# Main_PCB_v2_2.net
KiCad netlist of a schematic drawn in EAGLE
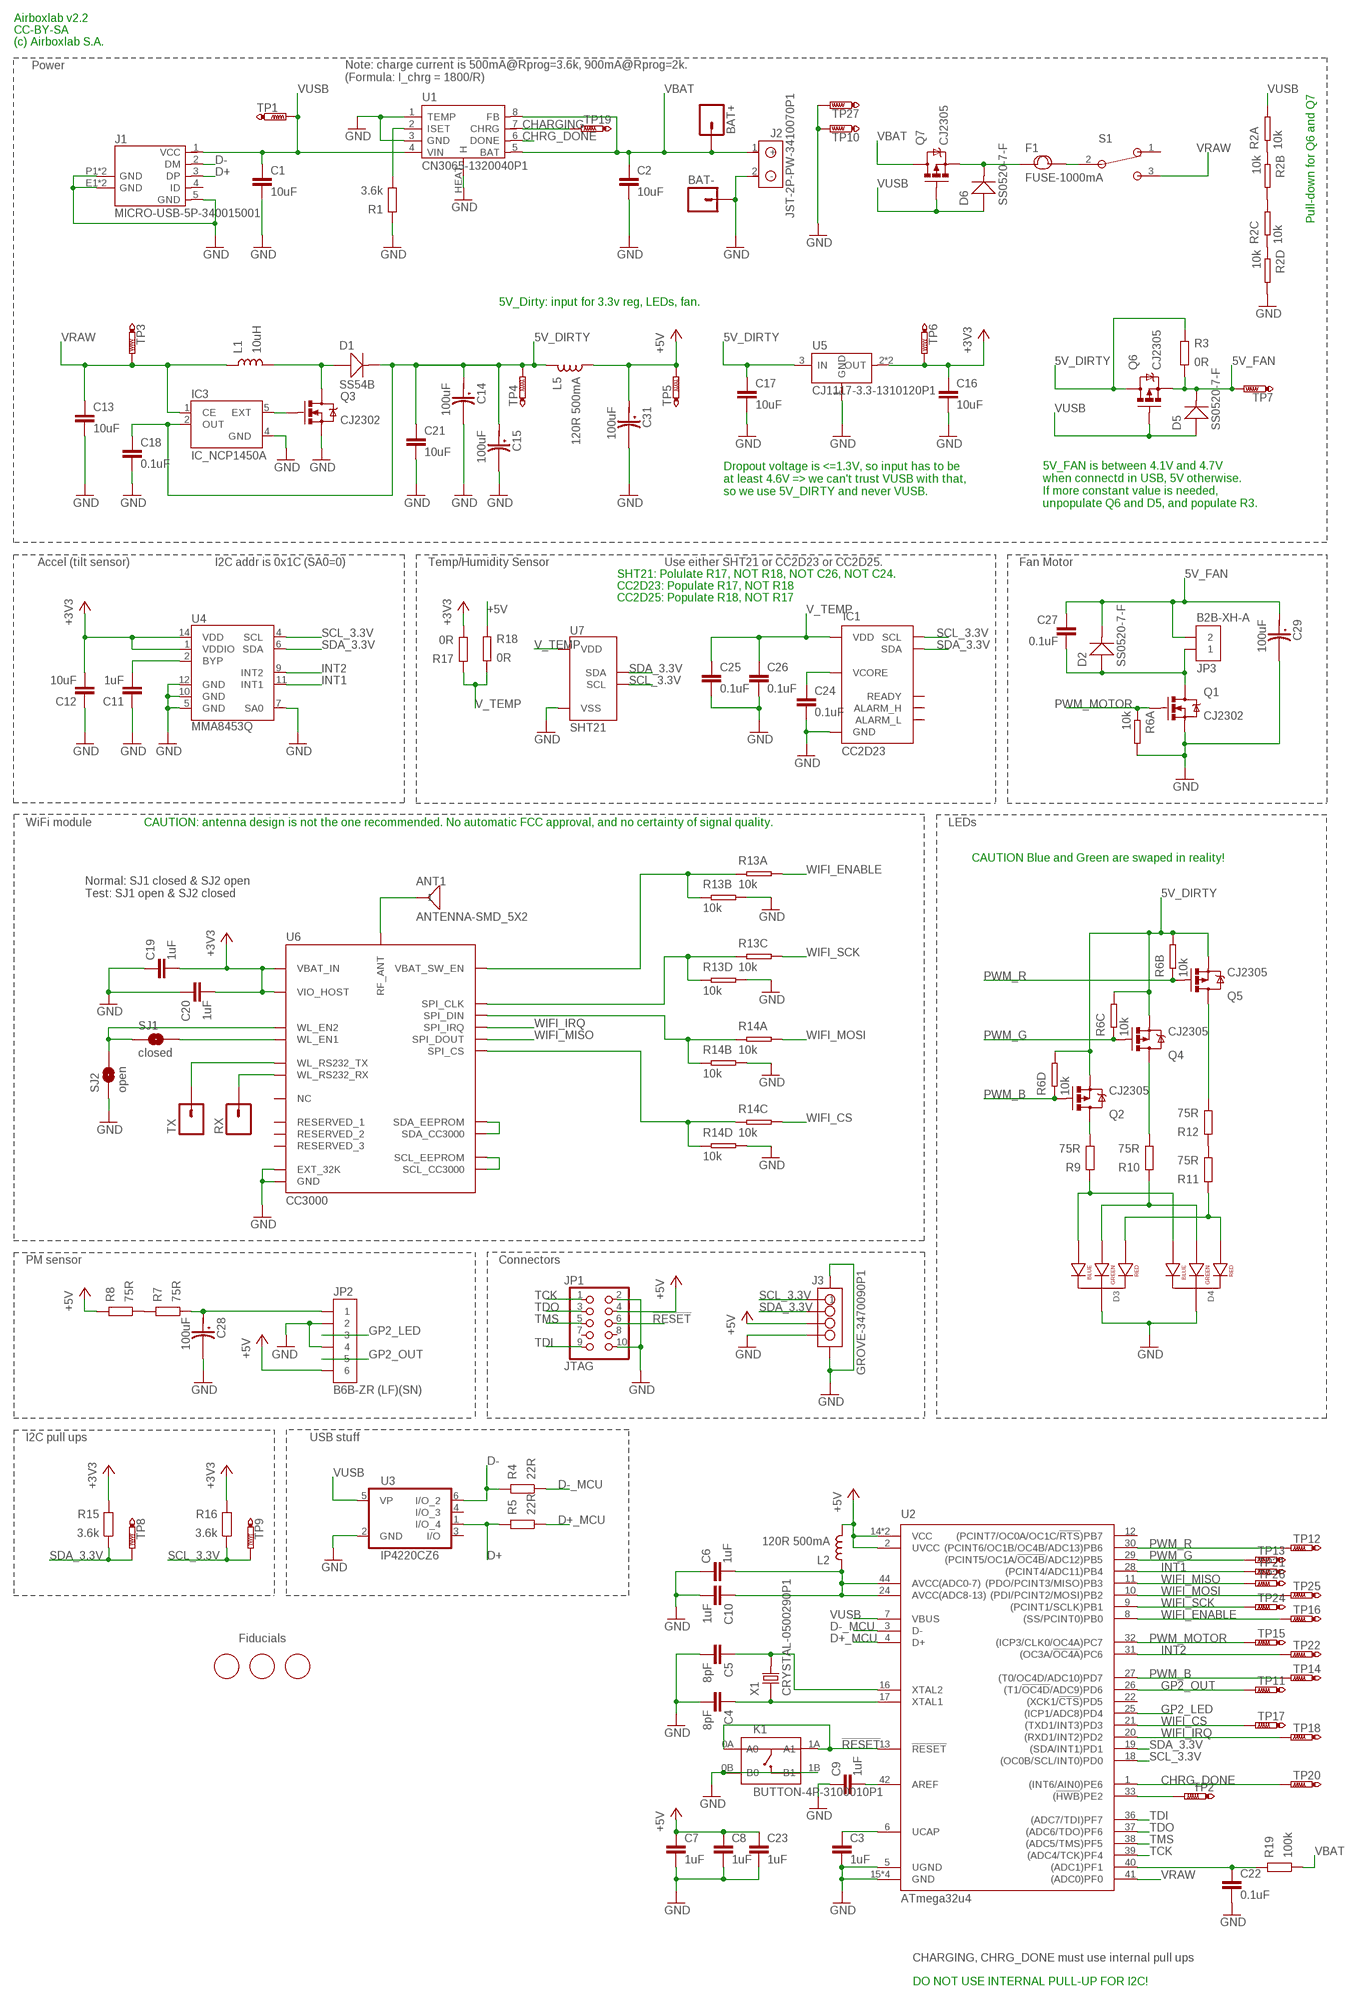
[diagram p0: schematic, sheet 1]

(export (version "E")
  (design (tool "Eeschema 10.0.6"))
  (components
    (comp (ref "ANT1")
      (value "ANTENNA-SMD_5X2")
      (footprint "eagle-import:ANTENNA_SMD_5X2")
      (libsource (lib "eagle-import") (part "ANTENNA-SMD_5X2"))
    )
    (comp (ref "BAT+")
      (value "M01PTH")
      (footprint "eagle-import:1X01")
      (libsource (lib "eagle-import") (part "M01PTH"))
    )
    (comp (ref "BAT-")
      (value "M01PTH")
      (footprint "eagle-import:1X01")
      (libsource (lib "eagle-import") (part "M01PTH"))
    )
    (comp (ref "C1")
      (value "10uF")
      (footprint "eagle-import:0805_N")
      (libsource (lib "eagle-import") (part "C0805"))
    )
    (comp (ref "C2")
      (value "10uF")
      (footprint "eagle-import:0805_N")
      (libsource (lib "eagle-import") (part "C0805"))
    )
    (comp (ref "C3")
      (value "1uF")
      (footprint "eagle-import:0603_N")
      (libsource (lib "eagle-import") (part "C0603"))
    )
    (comp (ref "C4")
      (value "8pF")
      (footprint "eagle-import:0603_N")
      (libsource (lib "eagle-import") (part "C0603"))
    )
    (comp (ref "C5")
      (value "8pF")
      (footprint "eagle-import:0603_N")
      (libsource (lib "eagle-import") (part "C0603"))
    )
    (comp (ref "C6")
      (value "1uF")
      (footprint "eagle-import:0603_N")
      (libsource (lib "eagle-import") (part "C0603"))
    )
    (comp (ref "C7")
      (value "1uF")
      (footprint "eagle-import:0603_N")
      (libsource (lib "eagle-import") (part "C0603"))
    )
    (comp (ref "C8")
      (value "1uF")
      (footprint "eagle-import:0603_N")
      (libsource (lib "eagle-import") (part "C0603"))
    )
    (comp (ref "C9")
      (value "1uF")
      (footprint "eagle-import:0603_N")
      (libsource (lib "eagle-import") (part "C0603"))
    )
    (comp (ref "C10")
      (value "1uF")
      (footprint "eagle-import:0603_N")
      (libsource (lib "eagle-import") (part "C0603"))
    )
    (comp (ref "C11")
      (value "1uF")
      (footprint "eagle-import:0603_N")
      (libsource (lib "eagle-import") (part "C0603"))
    )
    (comp (ref "C12")
      (value "10uF")
      (footprint "eagle-import:0805_N")
      (libsource (lib "eagle-import") (part "C0805"))
    )
    (comp (ref "C13")
      (value "10uF")
      (footprint "eagle-import:0805_N")
      (libsource (lib "eagle-import") (part "C0805"))
    )
    (comp (ref "C14")
      (value "100uF")
      (footprint "eagle-import:AVX-C")
      (libsource (lib "eagle-import") (part "C-POLAR-C"))
    )
    (comp (ref "C15")
      (value "100uF")
      (footprint "eagle-import:AVX-C")
      (libsource (lib "eagle-import") (part "C-POLAR-C"))
    )
    (comp (ref "C16")
      (value "10uF")
      (footprint "eagle-import:0805_N")
      (libsource (lib "eagle-import") (part "C0805"))
    )
    (comp (ref "C17")
      (value "10uF")
      (footprint "eagle-import:0805_N")
      (libsource (lib "eagle-import") (part "C0805"))
    )
    (comp (ref "C18")
      (value "0.1uF")
      (footprint "eagle-import:0603_N")
      (libsource (lib "eagle-import") (part "C0603"))
    )
    (comp (ref "C19")
      (value "1uF")
      (footprint "eagle-import:0603_N")
      (libsource (lib "eagle-import") (part "C0603"))
    )
    (comp (ref "C20")
      (value "1uF")
      (footprint "eagle-import:0603_N")
      (libsource (lib "eagle-import") (part "C0603"))
    )
    (comp (ref "C21")
      (value "10uF")
      (footprint "eagle-import:0805_N")
      (libsource (lib "eagle-import") (part "C0805"))
    )
    (comp (ref "C22")
      (value "0.1uF")
      (footprint "eagle-import:0603_N")
      (libsource (lib "eagle-import") (part "C0603"))
    )
    (comp (ref "C23")
      (value "1uF")
      (footprint "eagle-import:0603_N")
      (libsource (lib "eagle-import") (part "C0603"))
    )
    (comp (ref "C24")
      (value "0.1uF")
      (footprint "eagle-import:0603_N")
      (libsource (lib "eagle-import") (part "C0603"))
    )
    (comp (ref "C25")
      (value "0.1uF")
      (footprint "eagle-import:0603_N")
      (libsource (lib "eagle-import") (part "C0603"))
    )
    (comp (ref "C26")
      (value "0.1uF")
      (footprint "eagle-import:0603_N")
      (libsource (lib "eagle-import") (part "C0603"))
    )
    (comp (ref "C27")
      (value "0.1uF")
      (footprint "eagle-import:0603_N")
      (libsource (lib "eagle-import") (part "C0603"))
    )
    (comp (ref "C28")
      (value "100uF")
      (footprint "eagle-import:AVX-C")
      (libsource (lib "eagle-import") (part "C-POLAR-C"))
    )
    (comp (ref "C29")
      (value "100uF")
      (footprint "eagle-import:AVX-C")
      (libsource (lib "eagle-import") (part "C-POLAR-C"))
    )
    (comp (ref "C31")
      (value "100uF")
      (footprint "eagle-import:AVX-C")
      (libsource (lib "eagle-import") (part "C-POLAR-C"))
    )
    (comp (ref "D1")
      (value "SS54B")
      (footprint "eagle-import:SMB")
      (libsource (lib "eagle-import") (part "D-SMB"))
    )
    (comp (ref "D2")
      (value "SS0520-7-F")
      (footprint "eagle-import:SOD123")
      (libsource (lib "eagle-import") (part "D-SOD-123"))
    )
    (comp (ref "D3")
      (value "LED-RGB-CC-THRUCLEAR")
      (footprint "eagle-import:LED-RGB-THRU")
      (libsource (lib "eagle-import") (part "LED-RGB-CC-THRUCLEAR"))
    )
    (comp (ref "D4")
      (value "LED-RGB-CC-THRUCLEAR")
      (footprint "eagle-import:LED-RGB-THRU")
      (libsource (lib "eagle-import") (part "LED-RGB-CC-THRUCLEAR"))
    )
    (comp (ref "D5")
      (value "SS0520-7-F")
      (footprint "eagle-import:SOD123")
      (libsource (lib "eagle-import") (part "D-SOD-123"))
    )
    (comp (ref "D6")
      (value "SS0520-7-F")
      (footprint "eagle-import:SOD123")
      (libsource (lib "eagle-import") (part "D-SOD-123"))
    )
    (comp (ref "F1")
      (value "FUSE-1000mA")
      (footprint "eagle-import:F1206")
      (libsource (lib "eagle-import") (part "FUSE-1206"))
    )
    (comp (ref "IC1")
      (value "CC2D23")
      (footprint "eagle-import:CC2DXX")
      (libsource (lib "eagle-import") (part "CC2DXX"))
    )
    (comp (ref "IC3")
      (value "IC_NCP1450A")
      (footprint "eagle-import:SOT-23-5_N")
      (libsource (lib "eagle-import") (part "IC_NCP1450A"))
    )
    (comp (ref "J1")
      (value "MICRO-USB-5P-340015001")
      (footprint "eagle-import:B-SMD-5P")
      (libsource (lib "eagle-import") (part "MICRO-USB-5P-340015001"))
    )
    (comp (ref "J2")
      (value "JST-2P-PW-3410070P1")
      (footprint "eagle-import:2P-2.0-90D")
      (libsource (lib "eagle-import") (part "JST-2P-PW-3410070P1"))
    )
    (comp (ref "J3")
      (value "GROVE-3470090P1")
      (footprint "eagle-import:4P-SMD-2.0")
      (libsource (lib "eagle-import") (part "GROVE-4P-2.0-SMD-FEMALE-REINFORCE-3470090P1"))
    )
    (comp (ref "JP1")
      (value "JTAG")
      (footprint "eagle-import:CONNECTOR_2.54MM_5X2_LOCK")
      (libsource (lib "eagle-import") (part "CONNECTOR_5X2_2.54MM_LOCK"))
    )
    (comp (ref "JP2")
      (value "B6B-ZR (LF)(SN)")
      (footprint "eagle-import:CONNECTOR_B6B-ZR")
      (libsource (lib "eagle-import") (part "CONNECTOR_6X1-ZR-THT"))
    )
    (comp (ref "JP3")
      (value "B2B-XH-A")
      (footprint "eagle-import:CONNECTOR_B2B-XH-A")
      (libsource (lib "eagle-import") (part "CONNECTOR_2X1"))
    )
    (comp (ref "K1")
      (value "BUTTON-4P-3100010P1")
      (footprint "eagle-import:4P-SMD-6.0X6.0X5.0H")
      (libsource (lib "eagle-import") (part "BUTTON-4P-3100010P1"))
    )
    (comp (ref "L1")
      (value "10uH")
      (footprint "eagle-import:L_SRU8043")
      (libsource (lib "eagle-import") (part "L-SMD_8X8"))
    )
    (comp (ref "L2")
      (value "120R 500mA")
      (footprint "eagle-import:0603_N")
      (libsource (lib "eagle-import") (part "L0603"))
    )
    (comp (ref "L5")
      (value "120R 500mA")
      (footprint "eagle-import:0603_N")
      (libsource (lib "eagle-import") (part "L0603"))
    )
    (comp (ref "Q1")
      (value "CJ2302")
      (footprint "eagle-import:SOT-23-3_N_SSOT-3_N")
      (libsource (lib "eagle-import") (part "MOSFET_N_SOT23-3"))
    )
    (comp (ref "Q2")
      (value "CJ2305")
      (footprint "eagle-import:SOT-23-3_N_SSOT-3_N")
      (libsource (lib "eagle-import") (part "MOSFET_P_FDN308P"))
    )
    (comp (ref "Q3")
      (value "CJ2302")
      (footprint "eagle-import:SOT-23-3_N_SSOT-3_N")
      (libsource (lib "eagle-import") (part "MOSFET_N_SOT23-3"))
    )
    (comp (ref "Q4")
      (value "CJ2305")
      (footprint "eagle-import:SOT-23-3_N_SSOT-3_N")
      (libsource (lib "eagle-import") (part "MOSFET_P_FDN308P"))
    )
    (comp (ref "Q5")
      (value "CJ2305")
      (footprint "eagle-import:SOT-23-3_N_SSOT-3_N")
      (libsource (lib "eagle-import") (part "MOSFET_P_FDN308P"))
    )
    (comp (ref "Q6")
      (value "CJ2305")
      (footprint "eagle-import:SOT-23-3_N_SSOT-3_N")
      (libsource (lib "eagle-import") (part "MOSFET_P_FDN308P"))
    )
    (comp (ref "Q7")
      (value "CJ2305")
      (footprint "eagle-import:SOT-23-3_N_SSOT-3_N")
      (libsource (lib "eagle-import") (part "MOSFET_P_FDN308P"))
    )
    (comp (ref "R1")
      (value "3.6k")
      (footprint "eagle-import:0603_N")
      (libsource (lib "eagle-import") (part "R0603"))
    )
    (comp (ref "R2")
      (value "10k")
      (footprint "eagle-import:R1206-8")
      (libsource (lib "eagle-import") (part "R-4R"))
    )
    (comp (ref "R3")
      (value "0R")
      (footprint "eagle-import:0603_N")
      (libsource (lib "eagle-import") (part "R0603"))
    )
    (comp (ref "R4")
      (value "22R")
      (footprint "eagle-import:0603_N")
      (libsource (lib "eagle-import") (part "R0603"))
    )
    (comp (ref "R5")
      (value "22R")
      (footprint "eagle-import:0603_N")
      (libsource (lib "eagle-import") (part "R0603"))
    )
    (comp (ref "R6")
      (value "10k")
      (footprint "eagle-import:R1206-8")
      (libsource (lib "eagle-import") (part "R-4R"))
    )
    (comp (ref "R7")
      (value "75R")
      (footprint "eagle-import:0603_N")
      (libsource (lib "eagle-import") (part "R0603"))
    )
    (comp (ref "R8")
      (value "75R")
      (footprint "eagle-import:0603_N")
      (libsource (lib "eagle-import") (part "R0603"))
    )
    (comp (ref "R9")
      (value "75R")
      (footprint "eagle-import:0603_N")
      (libsource (lib "eagle-import") (part "R0603"))
    )
    (comp (ref "R10")
      (value "75R")
      (footprint "eagle-import:0603_N")
      (libsource (lib "eagle-import") (part "R0603"))
    )
    (comp (ref "R11")
      (value "75R")
      (footprint "eagle-import:0603_N")
      (libsource (lib "eagle-import") (part "R0603"))
    )
    (comp (ref "R12")
      (value "75R")
      (footprint "eagle-import:0603_N")
      (libsource (lib "eagle-import") (part "R0603"))
    )
    (comp (ref "R13")
      (value "10k")
      (footprint "eagle-import:R1206-8")
      (libsource (lib "eagle-import") (part "R-4R"))
    )
    (comp (ref "R14")
      (value "10k")
      (footprint "eagle-import:R1206-8")
      (libsource (lib "eagle-import") (part "R-4R"))
    )
    (comp (ref "R15")
      (value "3.6k")
      (footprint "eagle-import:0603_N")
      (libsource (lib "eagle-import") (part "R0603"))
    )
    (comp (ref "R16")
      (value "3.6k")
      (footprint "eagle-import:0603_N")
      (libsource (lib "eagle-import") (part "R0603"))
    )
    (comp (ref "R17")
      (value "0R")
      (footprint "eagle-import:0603_N")
      (libsource (lib "eagle-import") (part "R0603"))
    )
    (comp (ref "R18")
      (value "0R")
      (footprint "eagle-import:0603_N")
      (libsource (lib "eagle-import") (part "R0603"))
    )
    (comp (ref "R19")
      (value "100k")
      (footprint "eagle-import:0603_N")
      (libsource (lib "eagle-import") (part "R0603"))
    )
    (comp (ref "RX")
      (value "M01PTH")
      (footprint "eagle-import:1X01")
      (libsource (lib "eagle-import") (part "M01PTH"))
    )
    (comp (ref "S1")
      (value "SWITCH_SPDT_ON-ON")
      (footprint "eagle-import:SWITCH_SPDT_OS102011MA1QN1")
      (libsource (lib "eagle-import") (part "SWITCH_SPDT_ON-ON"))
    )
    (comp (ref "SJ1")
      (value "closed")
      (footprint "eagle-import:SJ_2S-TRACE2")
      (libsource (lib "eagle-import") (part "SOLDERJUMPER2_TRACE2"))
    )
    (comp (ref "SJ2")
      (value "open")
      (footprint "eagle-import:SJ_2S-NO")
      (libsource (lib "eagle-import") (part "SOLDERJUMPER2NO"))
    )
    (comp (ref "TP1")
      (value "PTR1PAD1-13")
      (footprint "eagle-import:P1-13")
      (libsource (lib "eagle-import") (part "PTR1PAD1-13"))
    )
    (comp (ref "TP2")
      (value "PTR1B1,27")
      (footprint "eagle-import:B1,27")
      (libsource (lib "eagle-import") (part "PTR1B1,27"))
    )
    (comp (ref "TP3")
      (value "PTR1PAD1-13")
      (footprint "eagle-import:P1-13")
      (libsource (lib "eagle-import") (part "PTR1PAD1-13"))
    )
    (comp (ref "TP4")
      (value "PTR1PAD1-13")
      (footprint "eagle-import:P1-13")
      (libsource (lib "eagle-import") (part "PTR1PAD1-13"))
    )
    (comp (ref "TP5")
      (value "PTR1PAD1-13")
      (footprint "eagle-import:P1-13")
      (libsource (lib "eagle-import") (part "PTR1PAD1-13"))
    )
    (comp (ref "TP6")
      (value "PTR1PAD1-13")
      (footprint "eagle-import:P1-13")
      (libsource (lib "eagle-import") (part "PTR1PAD1-13"))
    )
    (comp (ref "TP7")
      (value "PTR1PAD1-13")
      (footprint "eagle-import:P1-13")
      (libsource (lib "eagle-import") (part "PTR1PAD1-13"))
    )
    (comp (ref "TP8")
      (value "PTR1PAD1-13")
      (footprint "eagle-import:P1-13")
      (libsource (lib "eagle-import") (part "PTR1PAD1-13"))
    )
    (comp (ref "TP9")
      (value "PTR1PAD1-13")
      (footprint "eagle-import:P1-13")
      (libsource (lib "eagle-import") (part "PTR1PAD1-13"))
    )
    (comp (ref "TP10")
      (value "PTR1PAD1-13")
      (footprint "eagle-import:P1-13")
      (libsource (lib "eagle-import") (part "PTR1PAD1-13"))
    )
    (comp (ref "TP11")
      (value "PTR1PAD1-13")
      (footprint "eagle-import:P1-13")
      (libsource (lib "eagle-import") (part "PTR1PAD1-13"))
    )
    (comp (ref "TP12")
      (value "PTR1B1,27")
      (footprint "eagle-import:B1,27")
      (libsource (lib "eagle-import") (part "PTR1B1,27"))
    )
    (comp (ref "TP13")
      (value "PTR1B1,27")
      (footprint "eagle-import:B1,27")
      (libsource (lib "eagle-import") (part "PTR1B1,27"))
    )
    (comp (ref "TP14")
      (value "PTR1B1,27")
      (footprint "eagle-import:B1,27")
      (libsource (lib "eagle-import") (part "PTR1B1,27"))
    )
    (comp (ref "TP15")
      (value "PTR1B1,27")
      (footprint "eagle-import:B1,27")
      (libsource (lib "eagle-import") (part "PTR1B1,27"))
    )
    (comp (ref "TP16")
      (value "PTR1B1,27")
      (footprint "eagle-import:B1,27")
      (libsource (lib "eagle-import") (part "PTR1B1,27"))
    )
    (comp (ref "TP17")
      (value "PTR1B1,27")
      (footprint "eagle-import:B1,27")
      (libsource (lib "eagle-import") (part "PTR1B1,27"))
    )
    (comp (ref "TP18")
      (value "PTR1B1,27")
      (footprint "eagle-import:B1,27")
      (libsource (lib "eagle-import") (part "PTR1B1,27"))
    )
    (comp (ref "TP19")
      (value "PTR1B1,27")
      (footprint "eagle-import:B1,27")
      (libsource (lib "eagle-import") (part "PTR1B1,27"))
    )
    (comp (ref "TP20")
      (value "PTR1B1,27")
      (footprint "eagle-import:B1,27")
      (libsource (lib "eagle-import") (part "PTR1B1,27"))
    )
    (comp (ref "TP21")
      (value "PTR1B1,27")
      (footprint "eagle-import:B1,27")
      (libsource (lib "eagle-import") (part "PTR1B1,27"))
    )
    (comp (ref "TP22")
      (value "PTR1B1,27")
      (footprint "eagle-import:B1,27")
      (libsource (lib "eagle-import") (part "PTR1B1,27"))
    )
    (comp (ref "TP24")
      (value "PTR1B1,27")
      (footprint "eagle-import:B1,27")
      (libsource (lib "eagle-import") (part "PTR1B1,27"))
    )
    (comp (ref "TP25")
      (value "PTR1B1,27")
      (footprint "eagle-import:B1,27")
      (libsource (lib "eagle-import") (part "PTR1B1,27"))
    )
    (comp (ref "TP26")
      (value "PTR1B1,27")
      (footprint "eagle-import:B1,27")
      (libsource (lib "eagle-import") (part "PTR1B1,27"))
    )
    (comp (ref "TP27")
      (value "PTR1PAD1-13Y")
      (footprint "eagle-import:P1-13Y")
      (libsource (lib "eagle-import") (part "PTR1PAD1-13Y"))
    )
    (comp (ref "TX")
      (value "M01PTH")
      (footprint "eagle-import:1X01")
      (libsource (lib "eagle-import") (part "M01PTH"))
    )
    (comp (ref "U$1")
      (value "FIDUCIAL")
      (footprint "eagle-import:FIDUCIAL_1MM")
      (libsource (lib "eagle-import") (part "FIDUCIAL"))
    )
    (comp (ref "U$2")
      (value "FIDUCIAL")
      (footprint "eagle-import:FIDUCIAL_1MM")
      (libsource (lib "eagle-import") (part "FIDUCIAL"))
    )
    (comp (ref "U$3")
      (value "FIDUCIAL")
      (footprint "eagle-import:FIDUCIAL_1MM")
      (libsource (lib "eagle-import") (part "FIDUCIAL"))
    )
    (comp (ref "U1")
      (value "CN3065-1320040P1")
      (footprint "eagle-import:DFN8")
      (libsource (lib "eagle-import") (part "CN3065-1320040P1"))
    )
    (comp (ref "U2")
      (value "ATmega32u4")
      (footprint "eagle-import:QFN-44_50P_N")
      (libsource (lib "eagle-import") (part "IC_ATMEGAXXU4-MU"))
    )
    (comp (ref "U3")
      (value "IP4220CZ6")
      (footprint "eagle-import:SOT95P275X110-6N")
      (libsource (lib "eagle-import") (part "IP4220CZ6"))
    )
    (comp (ref "U4")
      (value "MMA8453Q")
      (footprint "eagle-import:QFN-16_0.5MM")
      (libsource (lib "eagle-import") (part "MMA8452Q"))
    )
    (comp (ref "U5")
      (value "CJ1117-3.3-1310120P1")
      (footprint "eagle-import:SOT89")
      (libsource (lib "eagle-import") (part "CJ1117-3.3-1310120P1"))
    )
    (comp (ref "U6")
      (value "CC3000")
      (footprint "eagle-import:CC3000")
      (fields (field (name "AUTHOR") "Matt Bigarani") (field (name "MODIFIED_BY") "Xevelabs"))
      (libsource (lib "eagle-import") (part "CC3000"))
    )
    (comp (ref "U7")
      (value "SHT21")
      (footprint "eagle-import:SHT2X")
      (libsource (lib "eagle-import") (part "SHT2X-21"))
    )
    (comp (ref "X1")
      (value "CRYSTAL-0500290P1")
      (footprint "eagle-import:2P-SMD-5.0X3.2")
      (libsource (lib "eagle-import") (part "CRYSTAL-0500290P1"))
    )
  )
  (nets
    (net (code "1") (name "+3V3") (class "Default")
      (node (ref "C12") (pin "2") (pinfunction "2_2") (pintype "passive"))
      (node (ref "C16") (pin "1") (pinfunction "1_1") (pintype "passive"))
      (node (ref "C19") (pin "2") (pinfunction "2_2") (pintype "passive"))
      (node (ref "C20") (pin "2") (pinfunction "2_2") (pintype "passive"))
      (node (ref "R15") (pin "2") (pinfunction "2_2") (pintype "passive"))
      (node (ref "R16") (pin "2") (pinfunction "2_2") (pintype "passive"))
      (node (ref "R17") (pin "1") (pinfunction "1_1") (pintype "passive"))
      (node (ref "TP6") (pin "TP") (pinfunction "TP_TP") (pintype "input"))
      (node (ref "U4") (pin "1") (pinfunction "VDDIO_1") (pintype "bidirectional"))
      (node (ref "U4") (pin "14") (pinfunction "VDD_14") (pintype "bidirectional"))
      (node (ref "U5") (pin "2") (pinfunction "OUT_2") (pintype "bidirectional"))
      (node (ref "U5") (pin "4") (pinfunction "OUT_4") (pintype "bidirectional"))
      (node (ref "U6") (pin "P$19") (pinfunction "VBAT_IN_P$19") (pintype "bidirectional"))
      (node (ref "U6") (pin "P$23") (pinfunction "VIO_HOST_P$23") (pintype "bidirectional"))
    )
    (net (code "2") (name "+5V") (class "Default")
      (node (ref "C23") (pin "1") (pinfunction "1_1") (pintype "passive"))
      (node (ref "C31") (pin "+") (pinfunction "1_+") (pintype "bidirectional"))
      (node (ref "C7") (pin "1") (pinfunction "1_1") (pintype "passive"))
      (node (ref "C8") (pin "1") (pinfunction "1_1") (pintype "passive"))
      (node (ref "J3") (pin "3") (pinfunction "3_3") (pintype "bidirectional"))
      (node (ref "JP1") (pin "4") (pinfunction "4_4") (pintype "passive"))
      (node (ref "JP2") (pin "P$6") (pinfunction "6_P$6") (pintype "bidirectional"))
      (node (ref "L2") (pin "2") (pinfunction "2_2") (pintype "passive"))
      (node (ref "L5") (pin "2") (pinfunction "2_2") (pintype "passive"))
      (node (ref "R18") (pin "2") (pinfunction "2_2") (pintype "passive"))
      (node (ref "R8") (pin "2") (pinfunction "2_2") (pintype "passive"))
      (node (ref "TP5") (pin "TP") (pinfunction "TP_TP") (pintype "input"))
      (node (ref "U2") (pin "14") (pinfunction "VCC_14") (pintype "power_in"))
      (node (ref "U2") (pin "2") (pinfunction "UVCC_2") (pintype "power_in"))
      (node (ref "U2") (pin "34") (pinfunction "VCC_34") (pintype "power_in"))
    )
    (net (code "3") (name "/5V_DIRTY") (class "Default")
      (node (ref "C14") (pin "+") (pinfunction "1_+") (pintype "bidirectional"))
      (node (ref "C15") (pin "+") (pinfunction "1_+") (pintype "bidirectional"))
      (node (ref "C17") (pin "1") (pinfunction "1_1") (pintype "passive"))
      (node (ref "C18") (pin "1") (pinfunction "1_1") (pintype "passive"))
      (node (ref "C21") (pin "1") (pinfunction "1_1") (pintype "passive"))
      (node (ref "D1") (pin "-") (pinfunction "-_-") (pintype "passive"))
      (node (ref "IC3") (pin "2") (pinfunction "OUT_2") (pintype "input"))
      (node (ref "L5") (pin "1") (pinfunction "1_1") (pintype "passive"))
      (node (ref "Q2") (pin "2") (pinfunction "S_2") (pintype "passive"))
      (node (ref "Q4") (pin "2") (pinfunction "S_2") (pintype "passive"))
      (node (ref "Q5") (pin "2") (pinfunction "S_2") (pintype "passive"))
      (node (ref "Q6") (pin "3") (pinfunction "D_3") (pintype "passive"))
      (node (ref "R3") (pin "2") (pinfunction "2_2") (pintype "passive"))
      (node (ref "R6") (pin "5") (pinfunction "2_5") (pintype "passive"))
      (node (ref "R6") (pin "6") (pinfunction "2_6") (pintype "passive"))
      (node (ref "R6") (pin "7") (pinfunction "2_7") (pintype "passive"))
      (node (ref "TP4") (pin "TP") (pinfunction "TP_TP") (pintype "input"))
      (node (ref "U5") (pin "3") (pinfunction "IN_3") (pintype "bidirectional"))
    )
    (net (code "4") (name "/5V_FAN") (class "Default")
      (node (ref "C27") (pin "1") (pinfunction "1_1") (pintype "passive"))
      (node (ref "C29") (pin "+") (pinfunction "1_+") (pintype "bidirectional"))
      (node (ref "D2") (pin "-") (pinfunction "-_-") (pintype "passive"))
      (node (ref "D5") (pin "-") (pinfunction "-_-") (pintype "passive"))
      (node (ref "JP3") (pin "2") (pinfunction "2_2") (pintype "bidirectional"))
      (node (ref "Q6") (pin "2") (pinfunction "S_2") (pintype "passive"))
      (node (ref "R3") (pin "1") (pinfunction "1_1") (pintype "passive"))
      (node (ref "TP7") (pin "TP") (pinfunction "TP_TP") (pintype "input"))
    )
    (net (code "5") (name "/CHARGING") (class "Default")
      (node (ref "TP19") (pin "TP") (pinfunction "TP_TP") (pintype "input"))
      (node (ref "U1") (pin "7") (pinfunction "CHRG_7") (pintype "bidirectional"))
    )
    (net (code "6") (name "/CHRG_DONE") (class "Default")
      (node (ref "TP20") (pin "TP") (pinfunction "TP_TP") (pintype "input"))
      (node (ref "U1") (pin "6") (pinfunction "DONE_6") (pintype "bidirectional"))
      (node (ref "U2") (pin "1") (pinfunction "(INT6/AIN0)PE6_1") (pintype "bidirectional"))
    )
    (net (code "7") (name "/D+") (class "Default")
      (node (ref "J1") (pin "3") (pinfunction "DP_3") (pintype "bidirectional"))
      (node (ref "R5") (pin "2") (pinfunction "2_2") (pintype "passive"))
      (node (ref "U3") (pin "1") (pinfunction "I/O_4_1") (pintype "bidirectional"))
    )
    (net (code "8") (name "/D+_MCU") (class "Default")
      (node (ref "R5") (pin "1") (pinfunction "1_1") (pintype "passive"))
      (node (ref "U2") (pin "4") (pinfunction "D+_4") (pintype "bidirectional"))
    )
    (net (code "9") (name "/D-") (class "Default")
      (node (ref "J1") (pin "2") (pinfunction "DM_2") (pintype "bidirectional"))
      (node (ref "R4") (pin "2") (pinfunction "2_2") (pintype "passive"))
      (node (ref "U3") (pin "6") (pinfunction "I/O_2_6") (pintype "bidirectional"))
    )
    (net (code "10") (name "/D-_MCU") (class "Default")
      (node (ref "R4") (pin "1") (pinfunction "1_1") (pintype "passive"))
      (node (ref "U2") (pin "3") (pinfunction "D-_3") (pintype "bidirectional"))
    )
    (net (code "11") (name "/GP2_LED") (class "Default")
      (node (ref "JP2") (pin "P$3") (pinfunction "3_P$3") (pintype "bidirectional"))
      (node (ref "U2") (pin "25") (pinfunction "(ICP1/ADC8)PD4_25") (pintype "bidirectional"))
    )
    (net (code "12") (name "/GP2_OUT") (class "Default")
      (node (ref "JP2") (pin "P$5") (pinfunction "5_P$5") (pintype "bidirectional"))
      (node (ref "TP11") (pin "TP") (pinfunction "TP_TP") (pintype "input"))
      (node (ref "U2") (pin "26") (pinfunction "(T1/~{OC4D}/ADC9)PD6_26") (pintype "bidirectional"))
    )
    (net (code "13") (name "/INT1") (class "Default")
      (node (ref "TP21") (pin "TP") (pinfunction "TP_TP") (pintype "input"))
      (node (ref "U2") (pin "28") (pinfunction "(PCINT4/ADC11)PB4_28") (pintype "bidirectional"))
      (node (ref "U4") (pin "11") (pinfunction "INT1_11") (pintype "bidirectional"))
    )
    (net (code "14") (name "/INT2") (class "Default")
      (node (ref "TP22") (pin "TP") (pinfunction "TP_TP") (pintype "input"))
      (node (ref "U2") (pin "31") (pinfunction "(OC3A/~{OC4A})PC6_31") (pintype "output"))
      (node (ref "U4") (pin "9") (pinfunction "INT2_9") (pintype "bidirectional"))
    )
    (net (code "15") (name "/PWM_B") (class "Default")
      (node (ref "Q2") (pin "1") (pinfunction "G_1") (pintype "passive"))
      (node (ref "R6") (pin "4") (pinfunction "1_4") (pintype "passive"))
      (node (ref "TP14") (pin "TP") (pinfunction "TP_TP") (pintype "input"))
      (node (ref "U2") (pin "27") (pinfunction "(T0/OC4D/ADC10)PD7_27") (pintype "bidirectional"))
    )
    (net (code "16") (name "/PWM_G") (class "Default")
      (node (ref "Q4") (pin "1") (pinfunction "G_1") (pintype "passive"))
      (node (ref "R6") (pin "3") (pinfunction "1_3") (pintype "passive"))
      (node (ref "TP13") (pin "TP") (pinfunction "TP_TP") (pintype "input"))
      (node (ref "U2") (pin "29") (pinfunction "(PCINT5/OC1A/~{OC4B}/ADC12)PB5_29") (pintype "bidirectional"))
    )
    (net (code "17") (name "/PWM_MOTOR") (class "Default")
      (node (ref "Q1") (pin "1") (pinfunction "G_1") (pintype "passive"))
      (node (ref "R6") (pin "1") (pinfunction "1_1") (pintype "passive"))
      (node (ref "TP15") (pin "TP") (pinfunction "TP_TP") (pintype "input"))
      (node (ref "U2") (pin "32") (pinfunction "(ICP3/CLK0/OC4A)PC7_32") (pintype "output"))
    )
    (net (code "18") (name "/PWM_R") (class "Default")
      (node (ref "Q5") (pin "1") (pinfunction "G_1") (pintype "passive"))
      (node (ref "R6") (pin "2") (pinfunction "1_2") (pintype "passive"))
      (node (ref "TP12") (pin "TP") (pinfunction "TP_TP") (pintype "input"))
      (node (ref "U2") (pin "30") (pinfunction "(PCINT6/OC1B/OC4B/ADC13)PB6_30") (pintype "bidirectional"))
    )
    (net (code "19") (name "/SCL_3.3V") (class "Default")
      (node (ref "IC1") (pin "P$4") (pinfunction "SCL_P$4") (pintype "bidirectional"))
      (node (ref "J3") (pin "1") (pinfunction "1_1") (pintype "bidirectional"))
      (node (ref "R16") (pin "1") (pinfunction "1_1") (pintype "passive"))
      (node (ref "TP9") (pin "TP") (pinfunction "TP_TP") (pintype "input"))
      (node (ref "U2") (pin "18") (pinfunction "(OC0B/SCL/INT0)PD0_18") (pintype "bidirectional"))
      (node (ref "U4") (pin "4") (pinfunction "SCL_4") (pintype "bidirectional"))
      (node (ref "U7") (pin "6") (pinfunction "SCL_6") (pintype "bidirectional"))
    )
    (net (code "20") (name "/SDA_3.3V") (class "Default")
      (node (ref "IC1") (pin "P$3") (pinfunction "SDA_P$3") (pintype "bidirectional"))
      (node (ref "J3") (pin "2") (pinfunction "2_2") (pintype "bidirectional"))
      (node (ref "R15") (pin "1") (pinfunction "1_1") (pintype "passive"))
      (node (ref "TP8") (pin "TP") (pinfunction "TP_TP") (pintype "input"))
      (node (ref "U2") (pin "19") (pinfunction "(SDA/INT1)PD1_19") (pintype "bidirectional"))
      (node (ref "U4") (pin "6") (pinfunction "SDA_6") (pintype "bidirectional"))
      (node (ref "U7") (pin "1") (pinfunction "SDA_1") (pintype "bidirectional"))
    )
    (net (code "21") (name "/TCK") (class "Default")
      (node (ref "JP1") (pin "1") (pinfunction "1_1") (pintype "passive"))
      (node (ref "U2") (pin "39") (pinfunction "(ADC4/TCK)PF4_39") (pintype "bidirectional"))
    )
    (net (code "22") (name "/TDI") (class "Default")
      (node (ref "JP1") (pin "9") (pinfunction "9_9") (pintype "passive"))
      (node (ref "U2") (pin "36") (pinfunction "(ADC7/TDI)PF7_36") (pintype "bidirectional"))
    )
    (net (code "23") (name "/TDO") (class "Default")
      (node (ref "JP1") (pin "3") (pinfunction "3_3") (pintype "passive"))
      (node (ref "U2") (pin "37") (pinfunction "(ADC6/TDO)PF6_37") (pintype "bidirectional"))
    )
    (net (code "24") (name "/TMS") (class "Default")
      (node (ref "JP1") (pin "5") (pinfunction "5_5") (pintype "passive"))
      (node (ref "U2") (pin "38") (pinfunction "(ADC5/TMS)PF5_38") (pintype "bidirectional"))
    )
    (net (code "25") (name "/VBAT") (class "Default")
      (node (ref "BAT+") (pin "1") (pinfunction "1_1") (pintype "passive"))
      (node (ref "C2") (pin "1") (pinfunction "1_1") (pintype "passive"))
      (node (ref "J2") (pin "1") (pinfunction "+_1") (pintype "bidirectional"))
      (node (ref "Q7") (pin "3") (pinfunction "D_3") (pintype "passive"))
      (node (ref "R19") (pin "1") (pinfunction "1_1") (pintype "passive"))
      (node (ref "U1") (pin "5") (pinfunction "BAT_5") (pintype "bidirectional"))
      (node (ref "U1") (pin "8") (pinfunction "FB_8") (pintype "input"))
    )
    (net (code "26") (name "/VRAW") (class "Default")
      (node (ref "C13") (pin "1") (pinfunction "1_1") (pintype "passive"))
      (node (ref "IC3") (pin "1") (pinfunction "CE_1") (pintype "power_in"))
      (node (ref "L1") (pin "P$1") (pinfunction "1_P$1") (pintype "passive"))
      (node (ref "S1") (pin "3") (pinfunction "3_3") (pintype "passive"))
      (node (ref "TP3") (pin "TP") (pinfunction "TP_TP") (pintype "input"))
      (node (ref "U2") (pin "41") (pinfunction "(ADC0)PF0_41") (pintype "bidirectional"))
    )
    (net (code "27") (name "/VUSB") (class "Default")
      (node (ref "C1") (pin "1") (pinfunction "1_1") (pintype "passive"))
      (node (ref "D5") (pin "+") (pinfunction "+_+") (pintype "passive"))
      (node (ref "D6") (pin "+") (pinfunction "+_+") (pintype "passive"))
      (node (ref "J1") (pin "1") (pinfunction "VCC_1") (pintype "bidirectional"))
      (node (ref "Q6") (pin "1") (pinfunction "G_1") (pintype "passive"))
      (node (ref "Q7") (pin "1") (pinfunction "G_1") (pintype "passive"))
      (node (ref "R2") (pin "8") (pinfunction "2_8") (pintype "passive"))
      (node (ref "TP1") (pin "TP") (pinfunction "TP_TP") (pintype "input"))
      (node (ref "U1") (pin "4") (pinfunction "VIN_4") (pintype "input"))
      (node (ref "U2") (pin "7") (pinfunction "VBUS_7") (pintype "passive"))
      (node (ref "U3") (pin "5") (pinfunction "VP_5") (pintype "power_in"))
    )
    (net (code "28") (name "/V_TEMP") (class "Default")
      (node (ref "C25") (pin "1") (pinfunction "1_1") (pintype "passive"))
      (node (ref "C26") (pin "1") (pinfunction "1_1") (pintype "passive"))
      (node (ref "IC1") (pin "P$7") (pinfunction "VDD_P$7") (pintype "bidirectional"))
      (node (ref "R17") (pin "2") (pinfunction "2_2") (pintype "passive"))
      (node (ref "R18") (pin "1") (pinfunction "1_1") (pintype "passive"))
      (node (ref "U7") (pin "5") (pinfunction "VDD_5") (pintype "power_in"))
    )
    (net (code "29") (name "/WIFI_CS") (class "Default")
      (node (ref "R14") (pin "6") (pinfunction "2_6") (pintype "passive"))
      (node (ref "TP17") (pin "TP") (pinfunction "TP_TP") (pintype "input"))
      (node (ref "U2") (pin "21") (pinfunction "(TXD1/INT3)PD3_21") (pintype "bidirectional"))
    )
    (net (code "30") (name "/WIFI_ENABLE") (class "Default")
      (node (ref "R13") (pin "8") (pinfunction "2_8") (pintype "passive"))
      (node (ref "TP16") (pin "TP") (pinfunction "TP_TP") (pintype "input"))
      (node (ref "U2") (pin "8") (pinfunction "(SS/PCINT0)PB0_8") (pintype "bidirectional"))
    )
    (net (code "31") (name "/WIFI_IRQ") (class "Default")
      (node (ref "TP18") (pin "TP") (pinfunction "TP_TP") (pintype "input"))
      (node (ref "U2") (pin "20") (pinfunction "(RXD1/INT2)PD2_20") (pintype "bidirectional"))
      (node (ref "U6") (pin "P$14") (pinfunction "SPI_IRQ_P$14") (pintype "bidirectional"))
    )
    (net (code "32") (name "/WIFI_MISO") (class "Default")
      (node (ref "TP26") (pin "TP") (pinfunction "TP_TP") (pintype "input"))
      (node (ref "U2") (pin "11") (pinfunction "(PDO/PCINT3/MISO)PB3_11") (pintype "bidirectional"))
      (node (ref "U6") (pin "P$13") (pinfunction "SPI_DOUT_P$13") (pintype "bidirectional"))
    )
    (net (code "33") (name "/WIFI_MOSI") (class "Default")
      (node (ref "R14") (pin "8") (pinfunction "2_8") (pintype "passive"))
      (node (ref "TP25") (pin "TP") (pinfunction "TP_TP") (pintype "input"))
      (node (ref "U2") (pin "10") (pinfunction "(PDI/PCINT2/MOSI)PB2_10") (pintype "bidirectional"))
    )
    (net (code "34") (name "/WIFI_SCK") (class "Default")
      (node (ref "R13") (pin "6") (pinfunction "2_6") (pintype "passive"))
      (node (ref "TP24") (pin "TP") (pinfunction "TP_TP") (pintype "input"))
      (node (ref "U2") (pin "9") (pinfunction "(PCINT1/SCLK)PB1_9") (pintype "bidirectional"))
    )
    (net (code "35") (name "/~{RESET}") (class "Default")
      (node (ref "JP1") (pin "6") (pinfunction "6_6") (pintype "passive"))
      (node (ref "K1") (pin "0A") (pinfunction "A0_0A") (pintype "bidirectional"))
      (node (ref "K1") (pin "1A") (pinfunction "A1_1A") (pintype "bidirectional"))
      (node (ref "U2") (pin "13") (pinfunction "~{RESET}_13") (pintype "bidirectional"))
    )
    (net (code "36") (name "GND") (class "Default")
      (node (ref "BAT-") (pin "1") (pinfunction "1_1") (pintype "passive"))
      (node (ref "C1") (pin "2") (pinfunction "2_2") (pintype "passive"))
      (node (ref "C10") (pin "2") (pinfunction "2_2") (pintype "passive"))
      (node (ref "C11") (pin "1") (pinfunction "1_1") (pintype "passive"))
      (node (ref "C12") (pin "1") (pinfunction "1_1") (pintype "passive"))
      (node (ref "C13") (pin "2") (pinfunction "2_2") (pintype "passive"))
      (node (ref "C14") (pin "-") (pinfunction "2_-") (pintype "bidirectional"))
      (node (ref "C15") (pin "-") (pinfunction "2_-") (pintype "bidirectional"))
      (node (ref "C16") (pin "2") (pinfunction "2_2") (pintype "passive"))
      (node (ref "C17") (pin "2") (pinfunction "2_2") (pintype "passive"))
      (node (ref "C18") (pin "2") (pinfunction "2_2") (pintype "passive"))
      (node (ref "C19") (pin "1") (pinfunction "1_1") (pintype "passive"))
      (node (ref "C2") (pin "2") (pinfunction "2_2") (pintype "passive"))
      (node (ref "C20") (pin "1") (pinfunction "1_1") (pintype "passive"))
      (node (ref "C21") (pin "2") (pinfunction "2_2") (pintype "passive"))
      (node (ref "C22") (pin "2") (pinfunction "2_2") (pintype "passive"))
      (node (ref "C23") (pin "2") (pinfunction "2_2") (pintype "passive"))
      (node (ref "C24") (pin "2") (pinfunction "2_2") (pintype "passive"))
      (node (ref "C25") (pin "2") (pinfunction "2_2") (pintype "passive"))
      (node (ref "C26") (pin "2") (pinfunction "2_2") (pintype "passive"))
      (node (ref "C28") (pin "-") (pinfunction "2_-") (pintype "bidirectional"))
      (node (ref "C29") (pin "-") (pinfunction "2_-") (pintype "bidirectional"))
      (node (ref "C3") (pin "2") (pinfunction "2_2") (pintype "passive"))
      (node (ref "C31") (pin "-") (pinfunction "2_-") (pintype "bidirectional"))
      (node (ref "C4") (pin "2") (pinfunction "2_2") (pintype "passive"))
      (node (ref "C5") (pin "2") (pinfunction "2_2") (pintype "passive"))
      (node (ref "C6") (pin "1") (pinfunction "1_1") (pintype "passive"))
      (node (ref "C7") (pin "2") (pinfunction "2_2") (pintype "passive"))
      (node (ref "C8") (pin "2") (pinfunction "2_2") (pintype "passive"))
      (node (ref "C9") (pin "1") (pinfunction "1_1") (pintype "passive"))
      (node (ref "D3") (pin "2") (pinfunction "CATHODE_2") (pintype "bidirectional"))
      (node (ref "D4") (pin "2") (pinfunction "CATHODE_2") (pintype "bidirectional"))
      (node (ref "IC1") (pin "P$6") (pinfunction "GND_P$6") (pintype "bidirectional"))
      (node (ref "IC3") (pin "4") (pinfunction "GND_4") (pintype "power_in"))
      (node (ref "J1") (pin "5") (pinfunction "GND_5") (pintype "bidirectional"))
      (node (ref "J1") (pin "E1") (pinfunction "GND_E1") (pintype "bidirectional"))
      (node (ref "J1") (pin "E2") (pinfunction "GND_E2") (pintype "bidirectional"))
      (node (ref "J1") (pin "P1") (pinfunction "GND_P1") (pintype "bidirectional"))
      (node (ref "J1") (pin "P2") (pinfunction "GND_P2") (pintype "bidirectional"))
      (node (ref "J2") (pin "2") (pinfunction "-_2") (pintype "bidirectional"))
      (node (ref "J3") (pin "4") (pinfunction "4_4") (pintype "bidirectional"))
      (node (ref "J3") (pin "SS1") (pinfunction "SS1_SS1") (pintype "bidirectional"))
      (node (ref "J3") (pin "SS2") (pinfunction "SS2_SS2") (pintype "bidirectional"))
      (node (ref "JP1") (pin "10") (pinfunction "10_10") (pintype "passive"))
      (node (ref "JP1") (pin "2") (pinfunction "2_2") (pintype "passive"))
      (node (ref "JP2") (pin "P$2") (pinfunction "2_P$2") (pintype "bidirectional"))
      (node (ref "JP2") (pin "P$4") (pinfunction "4_P$4") (pintype "bidirectional"))
      (node (ref "K1") (pin "0B") (pinfunction "B0_0B") (pintype "bidirectional"))
      (node (ref "K1") (pin "1B") (pinfunction "B1_1B") (pintype "bidirectional"))
      (node (ref "Q1") (pin "2") (pinfunction "S_2") (pintype "passive"))
      (node (ref "Q3") (pin "2") (pinfunction "S_2") (pintype "passive"))
      (node (ref "R1") (pin "2") (pinfunction "2_2") (pintype "passive"))
      (node (ref "R13") (pin "5") (pinfunction "2_5") (pintype "passive"))
      (node (ref "R13") (pin "7") (pinfunction "2_7") (pintype "passive"))
      (node (ref "R14") (pin "5") (pinfunction "2_5") (pintype "passive"))
      (node (ref "R14") (pin "7") (pinfunction "2_7") (pintype "passive"))
      (node (ref "R2") (pin "5") (pinfunction "2_5") (pintype "passive"))
      (node (ref "R6") (pin "8") (pinfunction "2_8") (pintype "passive"))
      (node (ref "SJ2") (pin "1") (pinfunction "1_1") (pintype "passive"))
      (node (ref "TP10") (pin "TP") (pinfunction "TP_TP") (pintype "input"))
      (node (ref "TP27") (pin "TP") (pinfunction "TP_TP") (pintype "input"))
      (node (ref "U1") (pin "1") (pinfunction "TEMP_1") (pintype "input"))
      (node (ref "U1") (pin "3") (pinfunction "GND_3") (pintype "power_in"))
      (node (ref "U1") (pin "HEAT") (pinfunction "H_HEAT") (pintype "bidirectional"))
      (node (ref "U2") (pin "15") (pinfunction "GND_15") (pintype "power_in"))
      (node (ref "U2") (pin "23") (pinfunction "GND_23") (pintype "power_in"))
      (node (ref "U2") (pin "35") (pinfunction "GND_35") (pintype "power_in"))
      (node (ref "U2") (pin "43") (pinfunction "GND_43") (pintype "power_in"))
      (node (ref "U2") (pin "5") (pinfunction "UGND_5") (pintype "power_in"))
      (node (ref "U3") (pin "2") (pinfunction "GND_2") (pintype "passive"))
      (node (ref "U4") (pin "10") (pinfunction "GND_10") (pintype "bidirectional"))
      (node (ref "U4") (pin "12") (pinfunction "GND_12") (pintype "bidirectional"))
      (node (ref "U4") (pin "5") (pinfunction "GND_5") (pintype "bidirectional"))
      (node (ref "U4") (pin "7") (pinfunction "SA0_7") (pintype "bidirectional"))
      (node (ref "U5") (pin "1") (pinfunction "GND_1") (pintype "bidirectional"))
      (node (ref "U6") (pin "P$1") (pinfunction "GND_P$1") (pintype "bidirectional"))
      (node (ref "U6") (pin "P$10") (pinfunction "GND_P$10") (pintype "bidirectional"))
      (node (ref "U6") (pin "P$11") (pinfunction "GND_P$11") (pintype "bidirectional"))
      (node (ref "U6") (pin "P$16") (pinfunction "GND_P$16") (pintype "bidirectional"))
      (node (ref "U6") (pin "P$18") (pinfunction "GND_P$18") (pintype "bidirectional"))
      (node (ref "U6") (pin "P$20") (pinfunction "GND_P$20") (pintype "bidirectional"))
      (node (ref "U6") (pin "P$21") (pinfunction "EXT_32K_P$21") (pintype "bidirectional"))
      (node (ref "U6") (pin "P$22") (pinfunction "GND_P$22") (pintype "bidirectional"))
      (node (ref "U6") (pin "P$25") (pinfunction "GND_P$25") (pintype "bidirectional"))
      (node (ref "U6") (pin "P$31") (pinfunction "GND_P$31") (pintype "bidirectional"))
      (node (ref "U6") (pin "P$32") (pinfunction "GND_P$32") (pintype "bidirectional"))
      (node (ref "U6") (pin "P$33") (pinfunction "GND_P$33") (pintype "bidirectional"))
      (node (ref "U6") (pin "P$34") (pinfunction "GND_P$34") (pintype "bidirectional"))
      (node (ref "U6") (pin "P$36") (pinfunction "GND_P$36") (pintype "bidirectional"))
      (node (ref "U6") (pin "P$37") (pinfunction "GND_P$37") (pintype "bidirectional"))
      (node (ref "U6") (pin "P$38") (pinfunction "GND_P$38") (pintype "bidirectional"))
      (node (ref "U6") (pin "P$39") (pinfunction "GND_P$39") (pintype "bidirectional"))
      (node (ref "U6") (pin "P$40") (pinfunction "GND_P$40") (pintype "bidirectional"))
      (node (ref "U6") (pin "P$41") (pinfunction "GND_P$41") (pintype "bidirectional"))
      (node (ref "U6") (pin "P$42") (pinfunction "GND_P$42") (pintype "bidirectional"))
      (node (ref "U6") (pin "P$43") (pinfunction "GND_P$43") (pintype "bidirectional"))
      (node (ref "U6") (pin "P$44") (pinfunction "GND_P$44") (pintype "bidirectional"))
      (node (ref "U6") (pin "P$45") (pinfunction "GND_P$45") (pintype "bidirectional"))
      (node (ref "U6") (pin "P$46") (pinfunction "GND_P$46") (pintype "bidirectional"))
      (node (ref "U6") (pin "P$9") (pinfunction "GND_P$9") (pintype "bidirectional"))
      (node (ref "U7") (pin "0") (pinfunction "VSS_0") (pintype "power_in"))
      (node (ref "U7") (pin "2") (pinfunction "VSS_2") (pintype "power_in"))
    )
    (net (code "37") (name "Net-(C28-1)") (class "Default")
      (node (ref "C28") (pin "+") (pinfunction "1_+") (pintype "bidirectional"))
      (node (ref "JP2") (pin "P$1") (pinfunction "1_P$1") (pintype "bidirectional"))
      (node (ref "R7") (pin "1") (pinfunction "1_1") (pintype "passive"))
    )
    (net (code "38") (name "Net-(D3-BLUE_CATHODE)") (class "Default")
      (node (ref "D3") (pin "4") (pinfunction "BLUE_CATHODE_4") (pintype "bidirectional"))
      (node (ref "D4") (pin "4") (pinfunction "BLUE_CATHODE_4") (pintype "bidirectional"))
      (node (ref "R9") (pin "2") (pinfunction "2_2") (pintype "passive"))
    )
    (net (code "39") (name "Net-(D3-GREEN_CATHODE)") (class "Default")
      (node (ref "D3") (pin "3") (pinfunction "GREEN_CATHODE_3") (pintype "bidirectional"))
      (node (ref "D4") (pin "3") (pinfunction "GREEN_CATHODE_3") (pintype "bidirectional"))
      (node (ref "R10") (pin "2") (pinfunction "2_2") (pintype "passive"))
    )
    (net (code "40") (name "Net-(D3-RED_CATHODE)") (class "Default")
      (node (ref "D3") (pin "1") (pinfunction "RED_CATHODE_1") (pintype "bidirectional"))
      (node (ref "D4") (pin "1") (pinfunction "RED_CATHODE_1") (pintype "bidirectional"))
      (node (ref "R11") (pin "2") (pinfunction "2_2") (pintype "passive"))
    )
    (net (code "41") (name "Net-(F1-Pad2)") (class "Default")
      (node (ref "F1") (pin "2") (pinfunction "2_2") (pintype "bidirectional"))
      (node (ref "S1") (pin "2") (pinfunction "2_2") (pintype "passive"))
    )
    (net (code "42") (name "Net-(IC1-VCORE)") (class "Default")
      (node (ref "C24") (pin "1") (pinfunction "1_1") (pintype "passive"))
      (node (ref "IC1") (pin "P$5") (pinfunction "VCORE_P$5") (pintype "bidirectional"))
    )
    (net (code "43") (name "Net-(IC3-EXT)") (class "Default")
      (node (ref "IC3") (pin "5") (pinfunction "EXT_5") (pintype "power_in"))
      (node (ref "Q3") (pin "1") (pinfunction "G_1") (pintype "passive"))
    )
    (net (code "44") (name "Net-(L1-2)") (class "Default")
      (node (ref "D1") (pin "+") (pinfunction "+_+") (pintype "passive"))
      (node (ref "L1") (pin "P$2") (pinfunction "2_P$2") (pintype "passive"))
      (node (ref "Q3") (pin "3") (pinfunction "D_3") (pintype "passive"))
    )
    (net (code "45") (name "Net-(Q1-D)") (class "Default")
      (node (ref "C27") (pin "2") (pinfunction "2_2") (pintype "passive"))
      (node (ref "D2") (pin "+") (pinfunction "+_+") (pintype "passive"))
      (node (ref "JP3") (pin "1") (pinfunction "1_1") (pintype "bidirectional"))
      (node (ref "Q1") (pin "3") (pinfunction "D_3") (pintype "passive"))
    )
    (net (code "46") (name "Net-(Q2-D)") (class "Default")
      (node (ref "Q2") (pin "3") (pinfunction "D_3") (pintype "passive"))
      (node (ref "R9") (pin "1") (pinfunction "1_1") (pintype "passive"))
    )
    (net (code "47") (name "Net-(Q4-D)") (class "Default")
      (node (ref "Q4") (pin "3") (pinfunction "D_3") (pintype "passive"))
      (node (ref "R10") (pin "1") (pinfunction "1_1") (pintype "passive"))
    )
    (net (code "48") (name "Net-(Q5-D)") (class "Default")
      (node (ref "Q5") (pin "3") (pinfunction "D_3") (pintype "passive"))
      (node (ref "R12") (pin "1") (pinfunction "1_1") (pintype "passive"))
    )
    (net (code "49") (name "Net-(Q7-S)") (class "Default")
      (node (ref "D6") (pin "-") (pinfunction "-_-") (pintype "passive"))
      (node (ref "F1") (pin "1") (pinfunction "1_1") (pintype "bidirectional"))
      (node (ref "Q7") (pin "2") (pinfunction "S_2") (pintype "passive"))
    )
    (net (code "50") (name "Net-(R2B-1)") (class "Default")
      (node (ref "R2") (pin "1") (pinfunction "1_1") (pintype "passive"))
      (node (ref "R2") (pin "2") (pinfunction "1_2") (pintype "passive"))
    )
    (net (code "51") (name "Net-(R2B-2)") (class "Default")
      (node (ref "R2") (pin "6") (pinfunction "2_6") (pintype "passive"))
      (node (ref "R2") (pin "7") (pinfunction "2_7") (pintype "passive"))
    )
    (net (code "52") (name "Net-(R2C-1)") (class "Default")
      (node (ref "R2") (pin "3") (pinfunction "1_3") (pintype "passive"))
      (node (ref "R2") (pin "4") (pinfunction "1_4") (pintype "passive"))
    )
    (net (code "53") (name "Net-(R7-Pad2)") (class "Default")
      (node (ref "R7") (pin "2") (pinfunction "2_2") (pintype "passive"))
      (node (ref "R8") (pin "1") (pinfunction "1_1") (pintype "passive"))
    )
    (net (code "54") (name "Net-(R11-Pad1)") (class "Default")
      (node (ref "R11") (pin "1") (pinfunction "1_1") (pintype "passive"))
      (node (ref "R12") (pin "2") (pinfunction "2_2") (pintype "passive"))
    )
    (net (code "55") (name "Net-(R13B-1)") (class "Default")
      (node (ref "R13") (pin "1") (pinfunction "1_1") (pintype "passive"))
      (node (ref "R13") (pin "2") (pinfunction "1_2") (pintype "passive"))
      (node (ref "U6") (pin "P$26") (pinfunction "VBAT_SW_EN_P$26") (pintype "bidirectional"))
    )
    (net (code "56") (name "Net-(R13C-1)") (class "Default")
      (node (ref "R13") (pin "3") (pinfunction "1_3") (pintype "passive"))
      (node (ref "R13") (pin "4") (pinfunction "1_4") (pintype "passive"))
      (node (ref "U6") (pin "P$17") (pinfunction "SPI_CLK_P$17") (pintype "bidirectional"))
    )
    (net (code "57") (name "Net-(R14B-1)") (class "Default")
      (node (ref "R14") (pin "1") (pinfunction "1_1") (pintype "passive"))
      (node (ref "R14") (pin "2") (pinfunction "1_2") (pintype "passive"))
      (node (ref "U6") (pin "P$15") (pinfunction "SPI_DIN_P$15") (pintype "bidirectional"))
    )
    (net (code "58") (name "Net-(R14C-1)") (class "Default")
      (node (ref "R14") (pin "3") (pinfunction "1_3") (pintype "passive"))
      (node (ref "R14") (pin "4") (pinfunction "1_4") (pintype "passive"))
      (node (ref "U6") (pin "P$12") (pinfunction "SPI_CS_P$12") (pintype "bidirectional"))
    )
    (net (code "59") (name "Net-(U1-ISET)") (class "Default")
      (node (ref "R1") (pin "1") (pinfunction "1_1") (pintype "passive"))
      (node (ref "U1") (pin "2") (pinfunction "ISET_2") (pintype "bidirectional"))
    )
    (net (code "60") (name "Net-(U2-(ADC1)PF1)") (class "Default")
      (node (ref "C22") (pin "1") (pinfunction "1_1") (pintype "passive"))
      (node (ref "R19") (pin "2") (pinfunction "2_2") (pintype "passive"))
      (node (ref "U2") (pin "40") (pinfunction "(ADC1)PF1_40") (pintype "bidirectional"))
    )
    (net (code "61") (name "Net-(U2-(~{HWB})PE2)") (class "Default")
      (node (ref "TP2") (pin "TP") (pinfunction "TP_TP") (pintype "input"))
      (node (ref "U2") (pin "33") (pinfunction "(~{HWB})PE2_33") (pintype "bidirectional"))
    )
    (net (code "62") (name "Net-(U2-AREF)") (class "Default")
      (node (ref "C9") (pin "2") (pinfunction "2_2") (pintype "passive"))
      (node (ref "U2") (pin "42") (pinfunction "AREF_42") (pintype "passive"))
    )
    (net (code "63") (name "Net-(U2-AVCC(ADC0-7))") (class "Default")
      (node (ref "C10") (pin "1") (pinfunction "1_1") (pintype "passive"))
      (node (ref "C6") (pin "2") (pinfunction "2_2") (pintype "passive"))
      (node (ref "L2") (pin "1") (pinfunction "1_1") (pintype "passive"))
      (node (ref "U2") (pin "24") (pinfunction "AVCC(ADC8-13)_24") (pintype "power_in"))
      (node (ref "U2") (pin "44") (pinfunction "AVCC(ADC0-7)_44") (pintype "power_in"))
    )
    (net (code "64") (name "Net-(U2-UCAP)") (class "Default")
      (node (ref "C3") (pin "1") (pinfunction "1_1") (pintype "passive"))
      (node (ref "U2") (pin "6") (pinfunction "UCAP_6") (pintype "passive"))
    )
    (net (code "65") (name "Net-(U2-XTAL1)") (class "Default")
      (node (ref "C4") (pin "1") (pinfunction "1_1") (pintype "passive"))
      (node (ref "U2") (pin "17") (pinfunction "XTAL1_17") (pintype "bidirectional"))
      (node (ref "X1") (pin "1") (pinfunction "1_1") (pintype "passive"))
    )
    (net (code "66") (name "Net-(U2-XTAL2)") (class "Default")
      (node (ref "C5") (pin "1") (pinfunction "1_1") (pintype "passive"))
      (node (ref "U2") (pin "16") (pinfunction "XTAL2_16") (pintype "bidirectional"))
      (node (ref "X1") (pin "2") (pinfunction "2_2") (pintype "passive"))
    )
    (net (code "67") (name "Net-(U4-BYP)") (class "Default")
      (node (ref "C11") (pin "2") (pinfunction "2_2") (pintype "passive"))
      (node (ref "U4") (pin "2") (pinfunction "BYP_2") (pintype "bidirectional"))
    )
    (net (code "68") (name "Net-(U6-RF_ANT)") (class "Default")
      (node (ref "ANT1") (pin "1") (pinfunction "1_1") (pintype "bidirectional"))
      (node (ref "U6") (pin "P$35") (pinfunction "RF_ANT_P$35") (pintype "bidirectional"))
    )
    (net (code "69") (name "Net-(U6-SCL_CC3000)") (class "Default")
      (node (ref "U6") (pin "P$29") (pinfunction "SCL_EEPROM_P$29") (pintype "bidirectional"))
      (node (ref "U6") (pin "P$30") (pinfunction "SCL_CC3000_P$30") (pintype "bidirectional"))
    )
    (net (code "70") (name "Net-(U6-SDA_CC3000)") (class "Default")
      (node (ref "U6") (pin "P$27") (pinfunction "SDA_EEPROM_P$27") (pintype "bidirectional"))
      (node (ref "U6") (pin "P$28") (pinfunction "SDA_CC3000_P$28") (pintype "bidirectional"))
    )
    (net (code "71") (name "Net-(U6-WL_EN1)") (class "Default")
      (node (ref "SJ1") (pin "2") (pinfunction "2_2") (pintype "passive"))
      (node (ref "U6") (pin "P$7") (pinfunction "WL_EN1_P$7") (pintype "bidirectional"))
    )
    (net (code "72") (name "Net-(U6-WL_EN2)") (class "Default")
      (node (ref "SJ1") (pin "1") (pinfunction "1_1") (pintype "passive"))
      (node (ref "SJ2") (pin "2") (pinfunction "2_2") (pintype "passive"))
      (node (ref "U6") (pin "P$5") (pinfunction "WL_EN2_P$5") (pintype "bidirectional"))
    )
    (net (code "73") (name "Net-(U6-WL_RS232_RX)") (class "Default")
      (node (ref "RX") (pin "1") (pinfunction "1_1") (pintype "passive"))
      (node (ref "U6") (pin "P$8") (pinfunction "WL_RS232_RX_P$8") (pintype "bidirectional"))
    )
    (net (code "74") (name "Net-(U6-WL_RS232_TX)") (class "Default")
      (node (ref "TX") (pin "1") (pinfunction "1_1") (pintype "passive"))
      (node (ref "U6") (pin "P$6") (pinfunction "WL_RS232_TX_P$6") (pintype "bidirectional"))
    )
    (net (code "75") (name "unconnected-(IC1-ALARM_H-PadP$8)") (class "Default")
      (node (ref "IC1") (pin "P$8") (pinfunction "ALARM_H_P$8") (pintype "bidirectional"))
    )
    (net (code "76") (name "unconnected-(IC1-ALARM_L-PadP$1)") (class "Default")
      (node (ref "IC1") (pin "P$1") (pinfunction "ALARM_L_P$1") (pintype "bidirectional"))
    )
    (net (code "77") (name "unconnected-(IC1-READY-PadP$2)") (class "Default")
      (node (ref "IC1") (pin "P$2") (pinfunction "READY_P$2") (pintype "bidirectional"))
    )
    (net (code "78") (name "unconnected-(J1-ID-Pad4)") (class "Default")
      (node (ref "J1") (pin "4") (pinfunction "ID_4") (pintype "bidirectional"))
    )
    (net (code "79") (name "unconnected-(JP1-Pad7)") (class "Default")
      (node (ref "JP1") (pin "7") (pinfunction "7_7") (pintype "passive"))
    )
    (net (code "80") (name "unconnected-(JP1-Pad8)") (class "Default")
      (node (ref "JP1") (pin "8") (pinfunction "8_8") (pintype "passive"))
    )
    (net (code "81") (name "unconnected-(S1-Pad1)") (class "Default")
      (node (ref "S1") (pin "1") (pinfunction "1_1") (pintype "passive"))
    )
    (net (code "82") (name "unconnected-(U2-(PCINT7{slash}OC0A{slash}OC1C{slash}~{RTS})PB7-Pad12)") (class "Default")
      (node (ref "U2") (pin "12") (pinfunction "(PCINT7/OC0A/OC1C/~{RTS})PB7_12") (pintype "bidirectional"))
    )
    (net (code "83") (name "unconnected-(U2-(XCK1{slash}~{CTS})PD5-Pad22)") (class "Default")
      (node (ref "U2") (pin "22") (pinfunction "(XCK1/~{CTS})PD5_22") (pintype "bidirectional"))
    )
    (net (code "84") (name "unconnected-(U3-I{slash}O-Pad3)") (class "Default")
      (node (ref "U3") (pin "3") (pinfunction "I/O_3") (pintype "bidirectional"))
    )
    (net (code "85") (name "unconnected-(U3-I{slash}O_3-Pad4)") (class "Default")
      (node (ref "U3") (pin "4") (pinfunction "I/O_3_4") (pintype "bidirectional"))
    )
    (net (code "86") (name "unconnected-(U6-NC-PadP$3)") (class "Default")
      (node (ref "U6") (pin "P$3") (pinfunction "NC_P$3") (pintype "bidirectional"))
    )
    (net (code "87") (name "unconnected-(U6-RESERVED_1-PadP$2)") (class "Default")
      (node (ref "U6") (pin "P$2") (pinfunction "RESERVED_1_P$2") (pintype "bidirectional"))
    )
    (net (code "88") (name "unconnected-(U6-RESERVED_2-PadP$4)") (class "Default")
      (node (ref "U6") (pin "P$4") (pinfunction "RESERVED_2_P$4") (pintype "bidirectional"))
    )
    (net (code "89") (name "unconnected-(U6-RESERVED_3-PadP$24)") (class "Default")
      (node (ref "U6") (pin "P$24") (pinfunction "RESERVED_3_P$24") (pintype "bidirectional"))
    )
  )
)
